# AirLP.net
KiCad netlist of a schematic drawn in Altium Designer
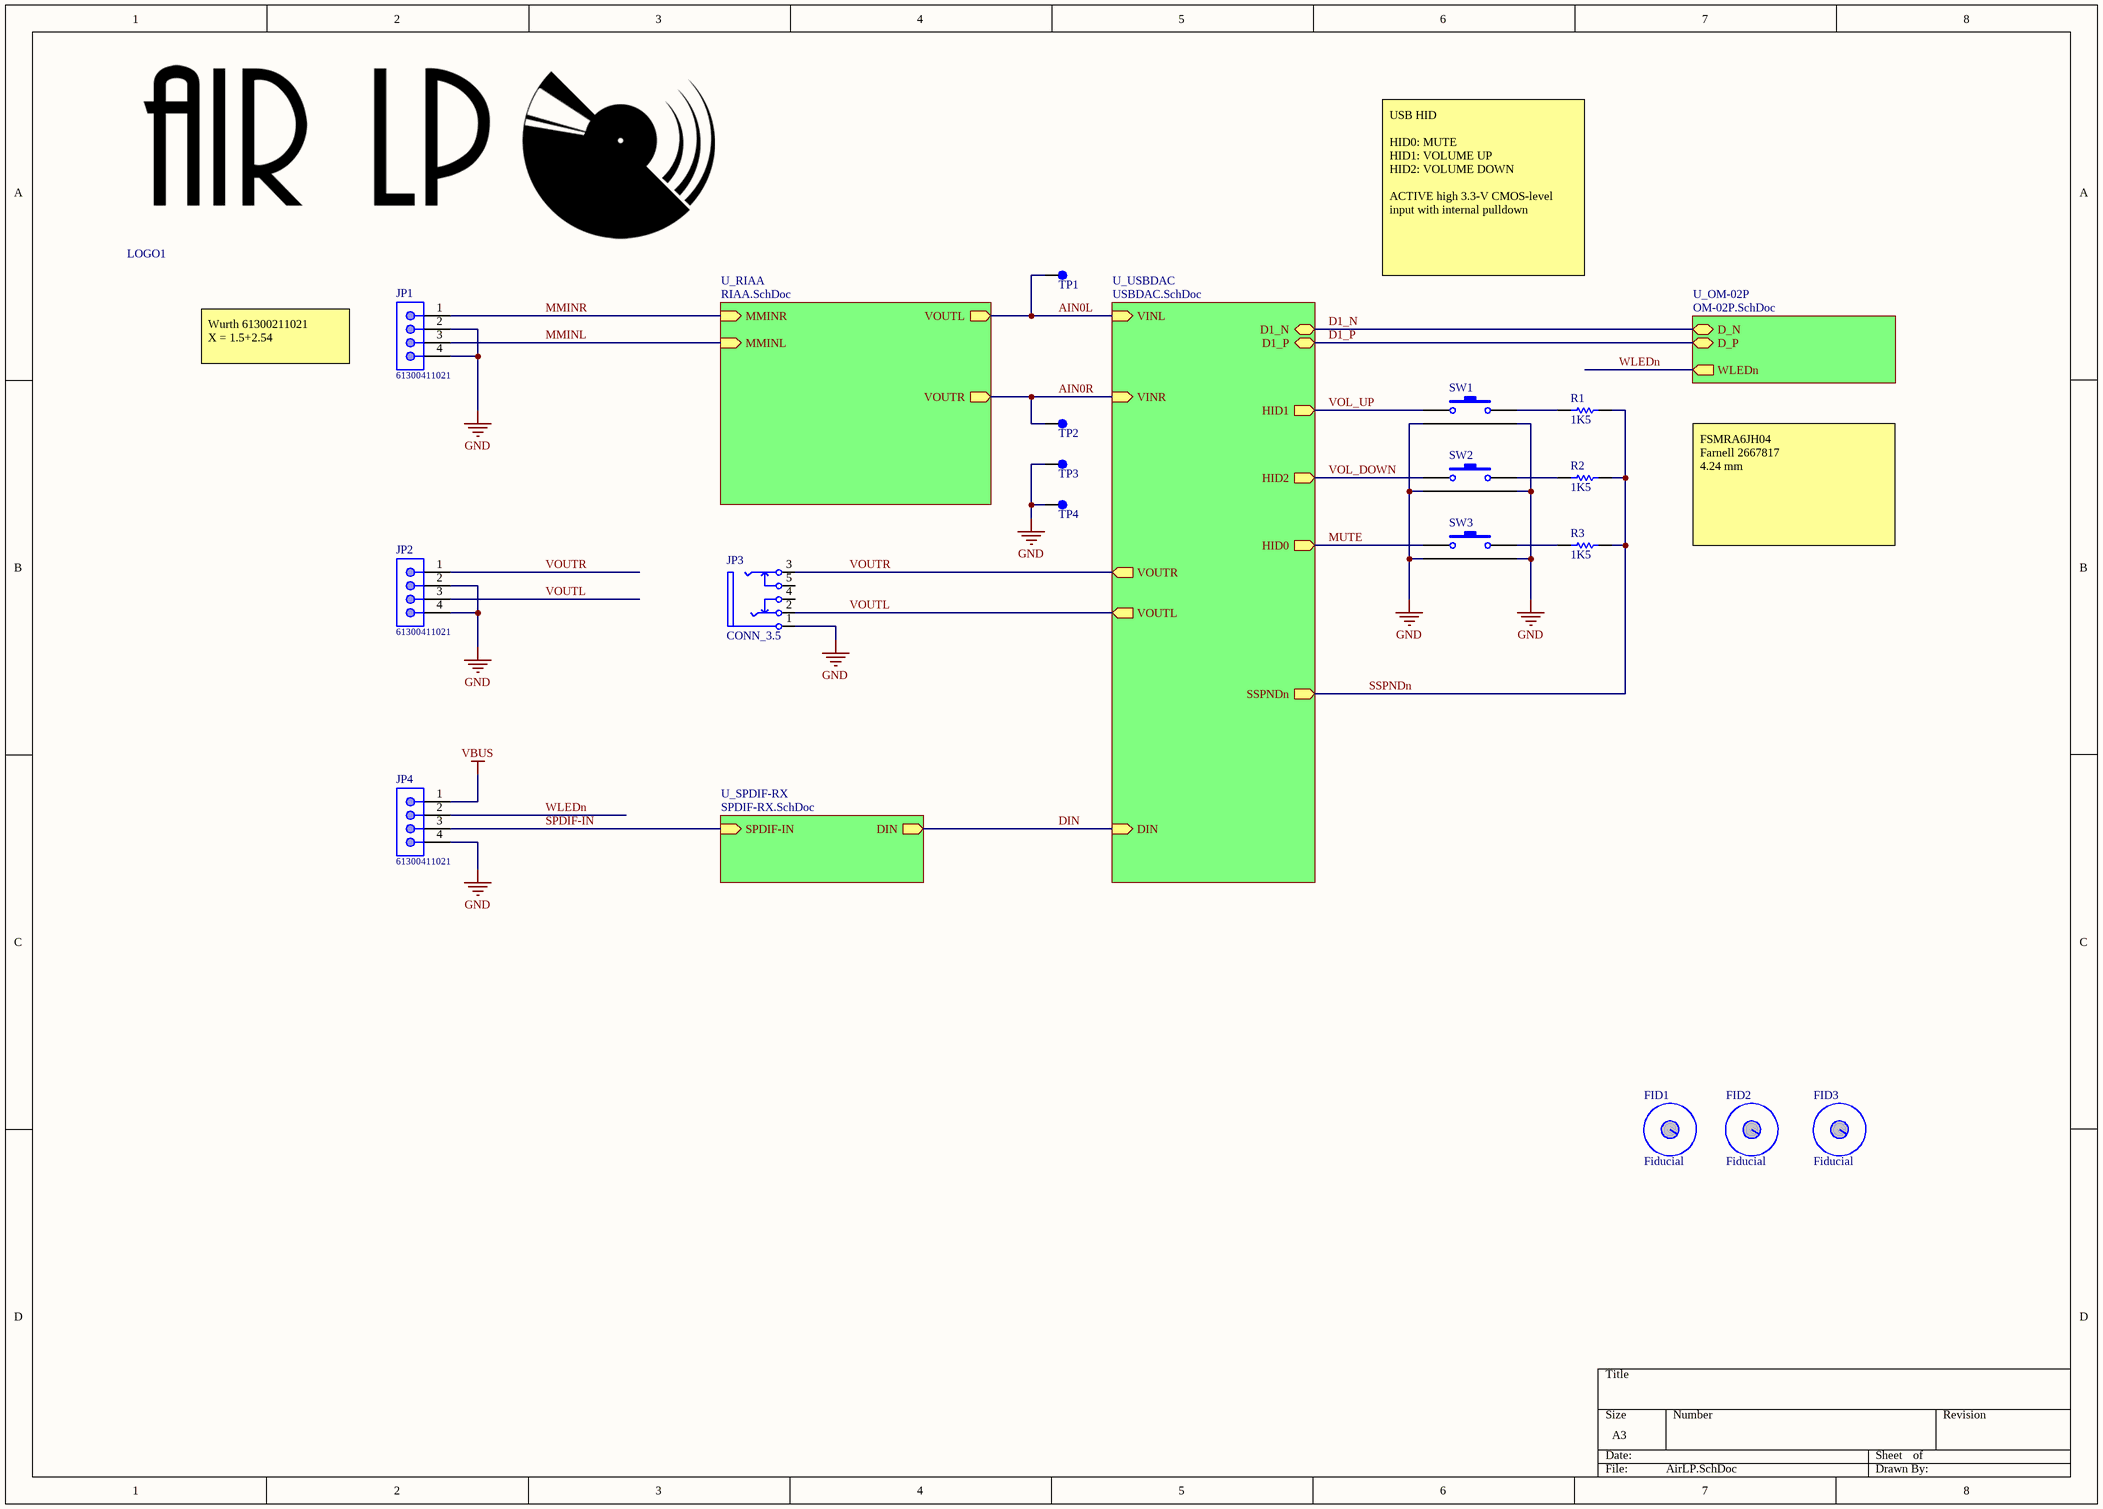
[diagram p0: AirLP.SchDoc]

(export (version "E")
  (design (tool "Eeschema 10.0.6"))
  (components
    (comp (ref "FID1")
      (value "Fiducial")
      (footprint "MECH_FID_PLUS")
      (libsource (lib "micun") (part "MECH_FIDUCIAL_PLUS"))
    )
    (comp (ref "FID2")
      (value "Fiducial")
      (footprint "MECH_FID_PLUS")
      (libsource (lib "micun") (part "MECH_FIDUCIAL_PLUS"))
    )
    (comp (ref "FID3")
      (value "Fiducial")
      (footprint "MECH_FID_PLUS")
      (libsource (lib "micun") (part "MECH_FIDUCIAL_PLUS"))
    )
    (comp (ref "JP1")
      (value "61300411021")
      (footprint "61300411021")
      (description "THT Angled Pin Header WR-PHD, Pitch 2.54 mm, Single Row, 4 pins")
      (fields (field (name "PUBLISHER") "Wurth Elektronik"))
      (libsource (lib "altium-import") (part "root_0_mirrored_61300411021_"))
    )
    (comp (ref "JP2")
      (value "61300411021")
      (footprint "61300411021")
      (description "THT Angled Pin Header WR-PHD, Pitch 2.54 mm, Single Row, 4 pins")
      (fields (field (name "PUBLISHER") "Wurth Elektronik"))
      (libsource (lib "altium-import") (part "root_0_mirrored_61300411021_"))
    )
    (comp (ref "JP3")
      (value "CONN_3.5")
      (footprint "CONN-3.5_LUMBERG_1503_09")
      (description "Jack Socket, 3.5mm, Thru-Hole, Horizontal, 3-Conductor with Tip open & Ring closed")
      (fields (field (name "MPN") "1503 09"))
      (libsource (lib "micun") (part "CONN_3.5_1503_09"))
    )
    (comp (ref "JP4")
      (value "61300411021")
      (footprint "61300411021")
      (description "THT Angled Pin Header WR-PHD, Pitch 2.54 mm, Single Row, 4 pins")
      (fields (field (name "PUBLISHER") "Wurth Elektronik"))
      (libsource (lib "altium-import") (part "root_0_mirrored_61300411021_"))
    )
    (comp (ref "LOGO1")
      (value "LOGO-AIRLP")
      (footprint "LOGO-AIR-LP")
      (description "LOGO AIR LP")
      (libsource (lib "micun") (part "LOGO-AIRLP"))
    )
    (comp (ref "R1")
      (value "1K5")
      (footprint "RESC0805(2012)_L")
      (description "0805 1.5KΩ ±5% 1/8W")
      (fields (field (name "TOLERANCE") "5%") (field (name "POWER") "125mW"))
      (libsource (lib "seeed") (part "RES_1K5_0805"))
    )
    (comp (ref "R2")
      (value "1K5")
      (footprint "RESC0805(2012)_L")
      (description "0805 1.5KΩ ±5% 1/8W")
      (fields (field (name "TOLERANCE") "5%") (field (name "POWER") "125mW"))
      (libsource (lib "seeed") (part "RES_1K5_0805"))
    )
    (comp (ref "R3")
      (value "1K5")
      (footprint "RESC0805(2012)_L")
      (description "0805 1.5KΩ ±5% 1/8W")
      (fields (field (name "TOLERANCE") "5%") (field (name "POWER") "125mW"))
      (libsource (lib "seeed") (part "RES_1K5_0805"))
    )
    (comp (ref "SW1")
      (value "SW_TACT_FSMRA2JH")
      (footprint "SW_FSMRA2JH")
      (description "SWITCH TACTILE SPST-NO 0.05A 12V")
      (fields (field (name "MPN") "FSMRA2JH"))
      (libsource (lib "micun") (part "SW_TACT_FSMRA2JH"))
    )
    (comp (ref "SW2")
      (value "SW_TACT_FSMRA2JH")
      (footprint "SW_FSMRA2JH")
      (description "SWITCH TACTILE SPST-NO 0.05A 12V")
      (fields (field (name "MPN") "FSMRA2JH"))
      (libsource (lib "micun") (part "SW_TACT_FSMRA2JH"))
    )
    (comp (ref "SW3")
      (value "SW_TACT_FSMRA2JH")
      (footprint "SW_FSMRA2JH")
      (description "SWITCH TACTILE SPST-NO 0.05A 12V")
      (fields (field (name "MPN") "FSMRA2JH"))
      (libsource (lib "micun") (part "SW_TACT_FSMRA2JH"))
    )
    (comp (ref "TP1")
      (value "MECH_Testpoint")
      (footprint "MECH_TP_39_mil")
      (description "Testpoint")
      (libsource (lib "micun") (part "MECH_Testpoint"))
    )
    (comp (ref "TP2")
      (value "MECH_Testpoint")
      (footprint "MECH_TP_39_mil")
      (description "Testpoint")
      (libsource (lib "micun") (part "MECH_Testpoint"))
    )
    (comp (ref "TP3")
      (value "MECH_Testpoint")
      (footprint "MECH_TP_39_mil")
      (description "Testpoint")
      (libsource (lib "micun") (part "MECH_Testpoint"))
    )
    (comp (ref "TP4")
      (value "MECH_Testpoint")
      (footprint "MECH_TP_39_mil")
      (description "Testpoint")
      (libsource (lib "micun") (part "MECH_Testpoint"))
    )
  )
  (nets
    (net (code "1") (name "/AIN0L") (class "Default")
      (node (ref "TP1") (pin "1") (pinfunction "Pin1_1") (pintype "passive"))
    )
    (net (code "2") (name "/AIN0R") (class "Default")
      (node (ref "TP2") (pin "1") (pinfunction "Pin1_1") (pintype "passive"))
    )
    (net (code "6") (name "/MMINL") (class "Default")
      (node (ref "JP1") (pin "3") (pinfunction "3_3") (pintype "passive"))
    )
    (net (code "7") (name "/MMINR") (class "Default")
      (node (ref "JP1") (pin "1") (pinfunction "1_1") (pintype "passive"))
    )
    (net (code "8") (name "/MUTE") (class "Default")
      (node (ref "SW3") (pin "1") (pinfunction "1_1") (pintype "passive"))
    )
    (net (code "9") (name "/SPDIF-IN") (class "Default")
      (node (ref "JP4") (pin "3") (pinfunction "3_3") (pintype "passive"))
    )
    (net (code "10") (name "/SSPNDn") (class "Default")
      (node (ref "R1") (pin "2") (pinfunction "2_2") (pintype "passive"))
      (node (ref "R2") (pin "2") (pinfunction "2_2") (pintype "passive"))
      (node (ref "R3") (pin "2") (pinfunction "2_2") (pintype "passive"))
    )
    (net (code "11") (name "/VOL_DOWN") (class "Default")
      (node (ref "SW2") (pin "1") (pinfunction "1_1") (pintype "passive"))
    )
    (net (code "12") (name "/VOL_UP") (class "Default")
      (node (ref "SW1") (pin "1") (pinfunction "1_1") (pintype "passive"))
    )
    (net (code "13") (name "/VOUTL") (class "Default")
      (node (ref "JP2") (pin "3") (pinfunction "3_3") (pintype "passive"))
      (node (ref "JP3") (pin "2") (pinfunction "T_2") (pintype "passive"))
    )
    (net (code "14") (name "/VOUTR") (class "Default")
      (node (ref "JP2") (pin "1") (pinfunction "1_1") (pintype "passive"))
      (node (ref "JP3") (pin "3") (pinfunction "RN_3") (pintype "passive"))
    )
    (net (code "15") (name "/WLEDn") (class "Default")
      (node (ref "JP4") (pin "2") (pinfunction "2_2") (pintype "passive"))
    )
    (net (code "16") (name "GND") (class "Default")
      (node (ref "JP1") (pin "2") (pinfunction "2_2") (pintype "passive"))
      (node (ref "JP1") (pin "4") (pinfunction "4_4") (pintype "passive"))
      (node (ref "JP2") (pin "2") (pinfunction "2_2") (pintype "passive"))
      (node (ref "JP2") (pin "4") (pinfunction "4_4") (pintype "passive"))
      (node (ref "JP3") (pin "1") (pinfunction "S_1") (pintype "passive"))
      (node (ref "JP4") (pin "4") (pinfunction "4_4") (pintype "passive"))
      (node (ref "SW1") (pin "3") (pinfunction "3_3") (pintype "passive"))
      (node (ref "SW1") (pin "4") (pinfunction "4_4") (pintype "passive"))
      (node (ref "SW2") (pin "3") (pinfunction "3_3") (pintype "passive"))
      (node (ref "SW2") (pin "4") (pinfunction "4_4") (pintype "passive"))
      (node (ref "SW3") (pin "3") (pinfunction "3_3") (pintype "passive"))
      (node (ref "SW3") (pin "4") (pinfunction "4_4") (pintype "passive"))
      (node (ref "TP3") (pin "1") (pinfunction "Pin1_1") (pintype "passive"))
      (node (ref "TP4") (pin "1") (pinfunction "Pin1_1") (pintype "passive"))
    )
    (net (code "17") (name "Net-(R1-Pad1)") (class "Default")
      (node (ref "R1") (pin "1") (pinfunction "1_1") (pintype "passive"))
      (node (ref "SW1") (pin "2") (pinfunction "2_2") (pintype "passive"))
    )
    (net (code "18") (name "Net-(R2-Pad1)") (class "Default")
      (node (ref "R2") (pin "1") (pinfunction "1_1") (pintype "passive"))
      (node (ref "SW2") (pin "2") (pinfunction "2_2") (pintype "passive"))
    )
    (net (code "19") (name "Net-(R3-Pad1)") (class "Default")
      (node (ref "R3") (pin "1") (pinfunction "1_1") (pintype "passive"))
      (node (ref "SW3") (pin "2") (pinfunction "2_2") (pintype "passive"))
    )
    (net (code "20") (name "VBUS") (class "Default")
      (node (ref "JP4") (pin "1") (pinfunction "1_1") (pintype "passive"))
    )
    (net (code "21") (name "unconnected-(JP3-Pad4)") (class "Default")
      (node (ref "JP3") (pin "4") (pinfunction "4_4") (pintype "passive"))
    )
    (net (code "22") (name "unconnected-(JP3-Pad5)") (class "Default")
      (node (ref "JP3") (pin "5") (pinfunction "5_5") (pintype "passive"))
    )
  )
)
